# SensorConn.net
KiCad netlist of a schematic drawn in Altium Designer
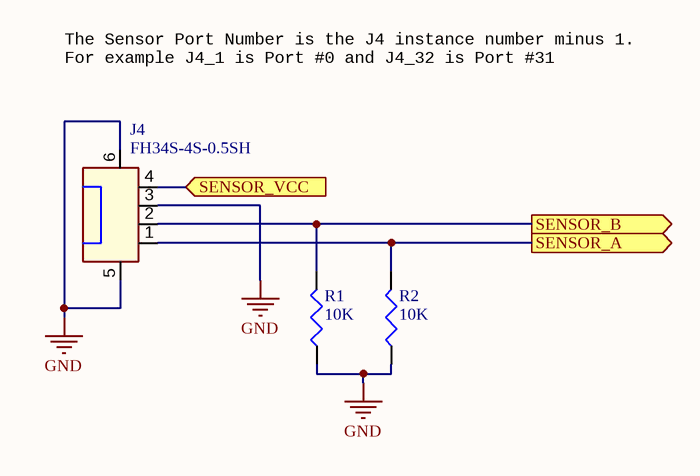
[diagram p0: SensorConn.SchDoc]

(export (version "E")
  (design (tool "Eeschema 10.0.6"))
  (components
    (comp (ref "J4")
      (value "FH34S-4S-0.5SH")
      (footprint "con_hirose_FH34SRJ-4S")
      (description "CONN FFC FPC 4POS 0.50MM R/A")
      (fields (field (name "MFG") "HIROSE"))
      (libsource (lib "SynapseLibrary") (part "HEADER 4 TABS"))
    )
    (comp (ref "R1")
      (value "10K")
      (footprint "0402-IPCsm_40")
      (description "RES 10.0K OHM 1/16W 5% 0402 SMD")
      (fields (field (name "TOLERANCE") "5.00%") (field (name "VOLTAGE") "50V"))
      (libsource (lib "SynapseLibrary") (part "RES"))
    )
    (comp (ref "R2")
      (value "10K")
      (footprint "0402-IPCsm_40")
      (description "RES 10.0K OHM 1/16W 5% 0402 SMD")
      (fields (field (name "TOLERANCE") "5.00%") (field (name "VOLTAGE") "50V"))
      (libsource (lib "SynapseLibrary") (part "RES"))
    )
  )
  (nets
    (net (code "1") (name "/SENSOR_A") (class "Default")
      (node (ref "J4") (pin "1") (pinfunction "1_1") (pintype "passive"))
      (node (ref "R2") (pin "2") (pinfunction "2_2") (pintype "passive"))
    )
    (net (code "2") (name "/SENSOR_B") (class "Default")
      (node (ref "J4") (pin "2") (pinfunction "2_2") (pintype "passive"))
      (node (ref "R1") (pin "2") (pinfunction "2_2") (pintype "passive"))
    )
    (net (code "3") (name "/SENSOR_VCC") (class "Default")
      (node (ref "J4") (pin "4") (pinfunction "4_4") (pintype "passive"))
    )
    (net (code "4") (name "GND") (class "Default")
      (node (ref "J4") (pin "3") (pinfunction "3_3") (pintype "passive"))
      (node (ref "J4") (pin "5") (pinfunction "TAB1_5") (pintype "passive"))
      (node (ref "J4") (pin "6") (pinfunction "TAB2_6") (pintype "passive"))
      (node (ref "R1") (pin "1") (pinfunction "1_1") (pintype "passive"))
      (node (ref "R2") (pin "1") (pinfunction "1_1") (pintype "passive"))
    )
  )
)
